# Distribution-board_2026-02-21.net
KiCad netlist of a schematic drawn in EasyEDA Pro
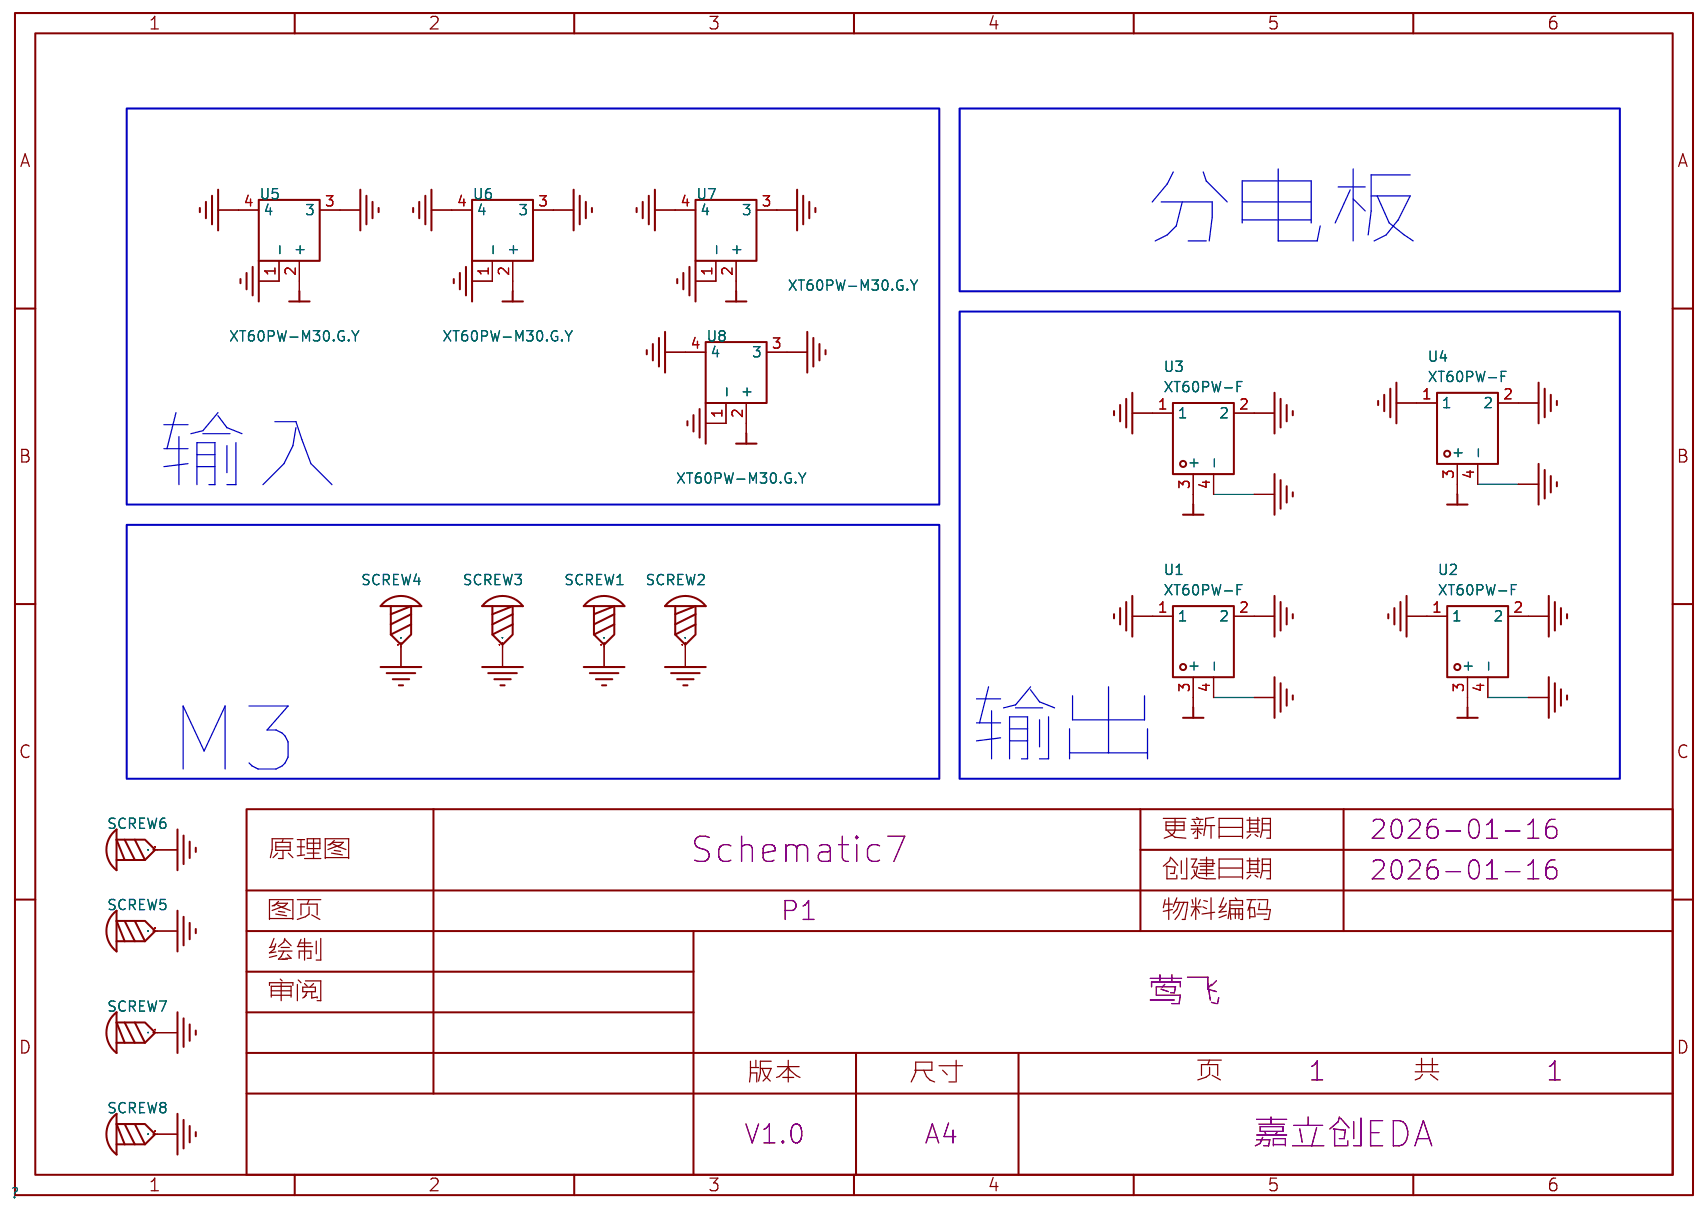
[diagram p0: schematic sheet]

(export (version "E")
  (design (tool "Eeschema 10.0.6"))
  (components
    (comp (ref "SCREW1")
      (value "~")
      (footprint "easyedapro:M3螺丝_1")
      (libsource (lib "easyedapro") (part "螺丝孔_1"))
    )
    (comp (ref "SCREW2")
      (value "~")
      (footprint "easyedapro:M3螺丝_1")
      (libsource (lib "easyedapro") (part "螺丝孔_1"))
    )
    (comp (ref "SCREW3")
      (value "~")
      (footprint "easyedapro:M3螺丝_1")
      (libsource (lib "easyedapro") (part "螺丝孔_1"))
    )
    (comp (ref "SCREW4")
      (value "~")
      (footprint "easyedapro:M3螺丝_1")
      (libsource (lib "easyedapro") (part "螺丝孔_1"))
    )
    (comp (ref "SCREW5")
      (value "~")
      (footprint "easyedapro:M3螺丝_1")
      (libsource (lib "easyedapro") (part "螺丝孔_1"))
    )
    (comp (ref "SCREW6")
      (value "~")
      (footprint "easyedapro:M3螺丝_1")
      (libsource (lib "easyedapro") (part "螺丝孔_1"))
    )
    (comp (ref "SCREW7")
      (value "~")
      (footprint "easyedapro:M3螺丝_1")
      (libsource (lib "easyedapro") (part "螺丝孔_1"))
    )
    (comp (ref "SCREW8")
      (value "~")
      (footprint "easyedapro:M3螺丝_1")
      (libsource (lib "easyedapro") (part "螺丝孔_1"))
    )
    (comp (ref "U1")
      (value "XT60PW-F")
      (footprint "easyedapro:TH_2P-XT60PW-F")
      (fields (field (name "Manufacturer") "AMASS(艾迈斯)"))
      (libsource (lib "easyedapro") (part "XT60PW-F_C428722"))
    )
    (comp (ref "U2")
      (value "XT60PW-F")
      (footprint "easyedapro:TH_2P-XT60PW-F")
      (fields (field (name "Manufacturer") "AMASS(艾迈斯)"))
      (libsource (lib "easyedapro") (part "XT60PW-F_C428722"))
    )
    (comp (ref "U3")
      (value "XT60PW-F")
      (footprint "easyedapro:TH_2P-XT60PW-F")
      (fields (field (name "Manufacturer") "AMASS(艾迈斯)"))
      (libsource (lib "easyedapro") (part "XT60PW-F_C428722"))
    )
    (comp (ref "U4")
      (value "XT60PW-F")
      (footprint "easyedapro:TH_2P-XT60PW-F")
      (fields (field (name "Manufacturer") "AMASS(艾迈斯)"))
      (libsource (lib "easyedapro") (part "XT60PW-F_C428722"))
    )
    (comp (ref "U5")
      (value "XT60PW-M30.G.Y")
      (footprint "easyedapro:CONN-TH_XT60PW-M")
      (libsource (lib "easyedapro") (part "XT60PW-M30.G.Y"))
    )
    (comp (ref "U6")
      (value "XT60PW-M30.G.Y")
      (footprint "easyedapro:CONN-TH_XT60PW-M")
      (libsource (lib "easyedapro") (part "XT60PW-M30.G.Y"))
    )
    (comp (ref "U7")
      (value "XT60PW-M30.G.Y")
      (footprint "easyedapro:CONN-TH_XT60PW-M")
      (libsource (lib "easyedapro") (part "XT60PW-M30.G.Y"))
    )
    (comp (ref "U8")
      (value "XT60PW-M30.G.Y")
      (footprint "easyedapro:CONN-TH_XT60PW-M")
      (libsource (lib "easyedapro") (part "XT60PW-M30.G.Y"))
    )
  )
  (nets
    (net (code "1") (name "12V") (class "Default")
      (node (ref "U1") (pin "3") (pinfunction "+_3") (pintype "unspecified"))
      (node (ref "U2") (pin "3") (pinfunction "+_3") (pintype "unspecified"))
      (node (ref "U3") (pin "3") (pinfunction "+_3") (pintype "unspecified"))
      (node (ref "U4") (pin "3") (pinfunction "+_3") (pintype "unspecified"))
      (node (ref "U5") (pin "2") (pinfunction "+_2") (pintype "unspecified"))
      (node (ref "U6") (pin "2") (pinfunction "+_2") (pintype "unspecified"))
      (node (ref "U7") (pin "2") (pinfunction "+_2") (pintype "unspecified"))
      (node (ref "U8") (pin "2") (pinfunction "+_2") (pintype "unspecified"))
    )
    (net (code "2") (name "GND") (class "Default")
      (node (ref "SCREW1") (pin "1") (pinfunction "1_1") (pintype "input"))
      (node (ref "SCREW2") (pin "1") (pinfunction "1_1") (pintype "input"))
      (node (ref "SCREW3") (pin "1") (pinfunction "1_1") (pintype "input"))
      (node (ref "SCREW4") (pin "1") (pinfunction "1_1") (pintype "input"))
      (node (ref "SCREW5") (pin "1") (pinfunction "1_1") (pintype "input"))
      (node (ref "SCREW6") (pin "1") (pinfunction "1_1") (pintype "input"))
      (node (ref "SCREW7") (pin "1") (pinfunction "1_1") (pintype "input"))
      (node (ref "SCREW8") (pin "1") (pinfunction "1_1") (pintype "input"))
      (node (ref "U1") (pin "1") (pinfunction "1_1") (pintype "unspecified"))
      (node (ref "U1") (pin "2") (pinfunction "2_2") (pintype "unspecified"))
      (node (ref "U1") (pin "4") (pinfunction "-_4") (pintype "unspecified"))
      (node (ref "U2") (pin "1") (pinfunction "1_1") (pintype "unspecified"))
      (node (ref "U2") (pin "2") (pinfunction "2_2") (pintype "unspecified"))
      (node (ref "U2") (pin "4") (pinfunction "-_4") (pintype "unspecified"))
      (node (ref "U3") (pin "1") (pinfunction "1_1") (pintype "unspecified"))
      (node (ref "U3") (pin "2") (pinfunction "2_2") (pintype "unspecified"))
      (node (ref "U3") (pin "4") (pinfunction "-_4") (pintype "unspecified"))
      (node (ref "U4") (pin "1") (pinfunction "1_1") (pintype "unspecified"))
      (node (ref "U4") (pin "2") (pinfunction "2_2") (pintype "unspecified"))
      (node (ref "U4") (pin "4") (pinfunction "-_4") (pintype "unspecified"))
      (node (ref "U5") (pin "1") (pinfunction "-_1") (pintype "unspecified"))
      (node (ref "U5") (pin "3") (pinfunction "3_3") (pintype "unspecified"))
      (node (ref "U5") (pin "4") (pinfunction "4_4") (pintype "unspecified"))
      (node (ref "U6") (pin "1") (pinfunction "-_1") (pintype "unspecified"))
      (node (ref "U6") (pin "3") (pinfunction "3_3") (pintype "unspecified"))
      (node (ref "U6") (pin "4") (pinfunction "4_4") (pintype "unspecified"))
      (node (ref "U7") (pin "1") (pinfunction "-_1") (pintype "unspecified"))
      (node (ref "U7") (pin "3") (pinfunction "3_3") (pintype "unspecified"))
      (node (ref "U7") (pin "4") (pinfunction "4_4") (pintype "unspecified"))
      (node (ref "U8") (pin "1") (pinfunction "-_1") (pintype "unspecified"))
      (node (ref "U8") (pin "3") (pinfunction "3_3") (pintype "unspecified"))
      (node (ref "U8") (pin "4") (pinfunction "4_4") (pintype "unspecified"))
    )
  )
)
